# Teensylu2-0_7.net
KiCad netlist of a schematic drawn in EAGLE
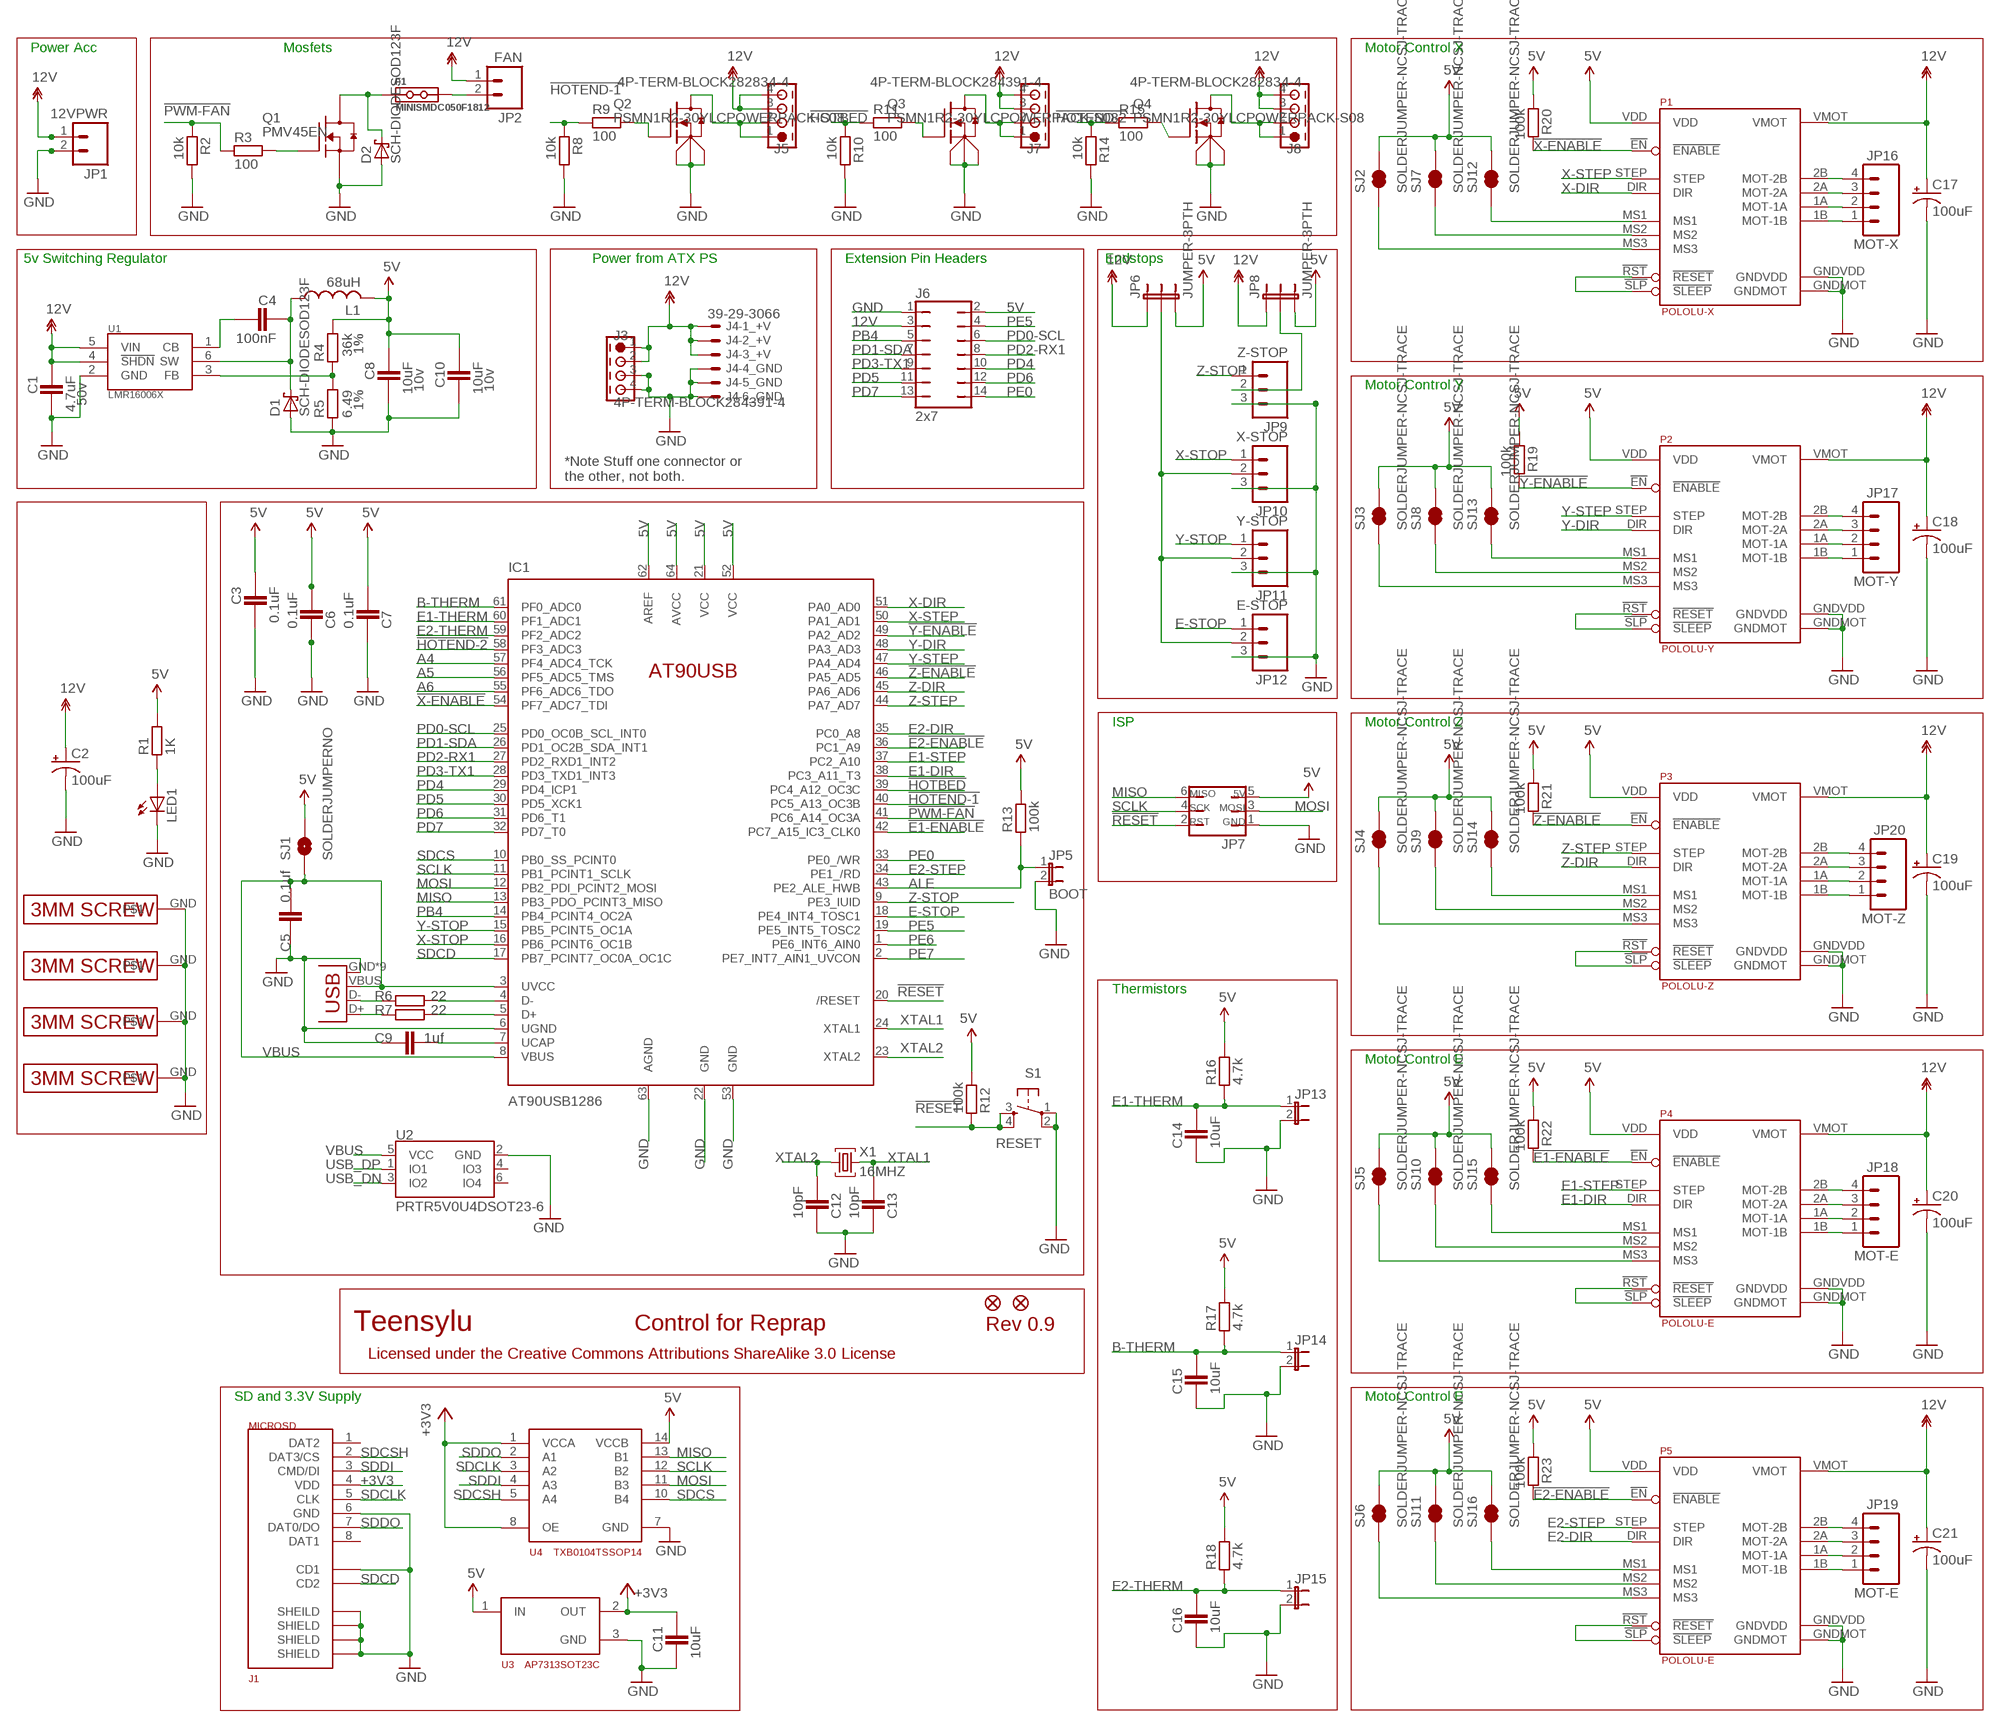
[diagram p0: schematic, sheet 1]

(export (version "E")
  (design (tool "Eeschema 10.0.6"))
  (components
    (comp (ref "C1")
      (value "4.7uF")
      (footprint "eagle-import:CAPC2012X145AN")
      (fields (field (name "VDC") "50v"))
      (libsource (lib "eagle-import") (part "CAPACITOR_0805"))
    )
    (comp (ref "C2")
      (value "100uF")
      (footprint "eagle-import:PANASONIC_D")
      (fields
        (field (name "MANUFACTURER") "Panasonic")
        (field (name "MANUFACTURER_PART_NUMBER") "EEE-FTH101XAP")
        (field (name "TOLERANCE") "20%")
      )
      (libsource (lib "eagle-import") (part "CPOL-USD"))
    )
    (comp (ref "C3")
      (value "0.1uF")
      (footprint "eagle-import:CAPC1608X92N")
      (libsource (lib "eagle-import") (part "CAPACITOR_0603"))
    )
    (comp (ref "C4")
      (value "100nF")
      (footprint "eagle-import:CAPC1608X92N")
      (libsource (lib "eagle-import") (part "CAPACITOR_0603"))
    )
    (comp (ref "C5")
      (value "0.1uf")
      (footprint "eagle-import:CAPC1608X92N")
      (libsource (lib "eagle-import") (part "CAPACITOR_0603"))
    )
    (comp (ref "C6")
      (value "0.1uF")
      (footprint "eagle-import:CAPC1608X92N")
      (libsource (lib "eagle-import") (part "CAPACITOR_0603"))
    )
    (comp (ref "C7")
      (value "0.1uF")
      (footprint "eagle-import:CAPC1608X92N")
      (libsource (lib "eagle-import") (part "CAPACITOR_0603"))
    )
    (comp (ref "C8")
      (value "10uF")
      (footprint "eagle-import:CAPC2012X145AN")
      (fields (field (name "VDC") "10v"))
      (libsource (lib "eagle-import") (part "CAPACITOR_0805"))
    )
    (comp (ref "C9")
      (value "1uf")
      (footprint "eagle-import:CAPC1608X92N")
      (libsource (lib "eagle-import") (part "CAPACITOR_0603"))
    )
    (comp (ref "C10")
      (value "10uF")
      (footprint "eagle-import:CAPC2012X145AN")
      (fields (field (name "VDC") "10v"))
      (libsource (lib "eagle-import") (part "CAPACITOR_0805"))
    )
    (comp (ref "C11")
      (value "10uF")
      (footprint "eagle-import:CAPC1608X92N")
      (libsource (lib "eagle-import") (part "CAPACITOR_0603"))
    )
    (comp (ref "C12")
      (value "10pF")
      (footprint "eagle-import:CAPC1608X92N")
      (libsource (lib "eagle-import") (part "CAPACITOR_0603"))
    )
    (comp (ref "C13")
      (value "10pF")
      (footprint "eagle-import:CAPC1608X92N")
      (libsource (lib "eagle-import") (part "CAPACITOR_0603"))
    )
    (comp (ref "C14")
      (value "10uF")
      (footprint "eagle-import:CAPC1608X92N")
      (libsource (lib "eagle-import") (part "CAPACITOR_0603"))
    )
    (comp (ref "C15")
      (value "10uF")
      (footprint "eagle-import:CAPC1608X92N")
      (libsource (lib "eagle-import") (part "CAPACITOR_0603"))
    )
    (comp (ref "C16")
      (value "10uF")
      (footprint "eagle-import:CAPC1608X92N")
      (libsource (lib "eagle-import") (part "CAPACITOR_0603"))
    )
    (comp (ref "C17")
      (value "100uF")
      (footprint "eagle-import:PANASONIC_D")
      (fields
        (field (name "MANUFACTURER") "Panasonic")
        (field (name "MANUFACTURER_PART_NUMBER") "EEE-FTH101XAP")
        (field (name "TOLERANCE") "20%")
      )
      (libsource (lib "eagle-import") (part "CPOL-USD"))
    )
    (comp (ref "C18")
      (value "100uF")
      (footprint "eagle-import:PANASONIC_D")
      (fields
        (field (name "MANUFACTURER") "Panasonic")
        (field (name "MANUFACTURER_PART_NUMBER") "EEE-FTH101XAP")
        (field (name "TOLERANCE") "20%")
      )
      (libsource (lib "eagle-import") (part "CPOL-USD"))
    )
    (comp (ref "C19")
      (value "100uF")
      (footprint "eagle-import:PANASONIC_D")
      (fields
        (field (name "MANUFACTURER") "Panasonic")
        (field (name "MANUFACTURER_PART_NUMBER") "EEE-FTH101XAP")
        (field (name "TOLERANCE") "20%")
      )
      (libsource (lib "eagle-import") (part "CPOL-USD"))
    )
    (comp (ref "C20")
      (value "100uF")
      (footprint "eagle-import:PANASONIC_D")
      (fields
        (field (name "MANUFACTURER") "Panasonic")
        (field (name "MANUFACTURER_PART_NUMBER") "EEE-FTH101XAP")
        (field (name "TOLERANCE") "20%")
      )
      (libsource (lib "eagle-import") (part "CPOL-USD"))
    )
    (comp (ref "C21")
      (value "100uF")
      (footprint "eagle-import:PANASONIC_D")
      (fields
        (field (name "MANUFACTURER") "Panasonic")
        (field (name "MANUFACTURER_PART_NUMBER") "EEE-FTH101XAP")
        (field (name "TOLERANCE") "20%")
      )
      (libsource (lib "eagle-import") (part "CPOL-USD"))
    )
    (comp (ref "D1")
      (value "SCH-DIODESOD123F")
      (footprint "eagle-import:SOD123F")
      (fields
        (field (name "MANUFACTURER") "NXP Semiconductors")
        (field (name "MANUFACTURER_PART_NUMBER") "PMEG4010CEH,115")
        (field (name "CURRENT") "1A")
        (field (name "MANUFACTURER_1") "NXP Semiconductors")
        (field (name "MANUFACTURER_PART_NUMBER_1") "PMEG4010CEH,115")
        (field (name "REVERSE_VOLTAGE") "40V")
      )
      (libsource (lib "eagle-import") (part "SCH-DIODESOD123F"))
    )
    (comp (ref "D2")
      (value "SCH-DIODESOD123F")
      (footprint "eagle-import:SOD123F")
      (fields
        (field (name "MANUFACTURER") "NXP Semiconductors")
        (field (name "MANUFACTURER_PART_NUMBER") "PMEG4010CEH,115")
        (field (name "CURRENT") "1A")
        (field (name "MANUFACTURER_1") "NXP Semiconductors")
      )
      (libsource (lib "eagle-import") (part "SCH-DIODESOD123F"))
    )
    (comp (ref "F1")
      (value "MINISMDC050F1812")
      (footprint "eagle-import:MINISMDC")
      (fields
        (field (name "MANUFACTURER") "TE Connectivity")
        (field (name "MANUFACTURER_PART_NUMBER") "MINISMDC050F-2")
      )
      (libsource (lib "eagle-import") (part "MINISMDC050F1812"))
    )
    (comp (ref "IC1")
      (value "AT90USB1286")
      (footprint "eagle-import:TQFP64-2")
      (libsource (lib "eagle-import") (part "AT90USB"))
    )
    (comp (ref "J1")
      (value "MICROSD")
      (footprint "eagle-import:AMPHENOL-MICROSD")
      (fields
        (field (name "MANUFACTURER") "Amphenol")
        (field (name "MANUFACTURER_PART_NUMBER") "114-00841-68")
      )
      (libsource (lib "eagle-import") (part "MICROSD"))
    )
    (comp (ref "J2")
      (value "USB-MICRO-PTH")
      (footprint "eagle-import:USB-MICROB-PTH")
      (fields (field (name "MANUFACTURER") "FCI") (field (name "MANUFACTURER_PART_NUMBER") "10118194-0001LF"))
      (libsource (lib "eagle-import") (part "USB-MICRO-PTH"))
    )
    (comp (ref "J3")
      (value "4P-TERM-BLOCK284391-4")
      (footprint "eagle-import:284391-4")
      (fields
        (field (name "MANUFACTURER") "TE Connectivity")
        (field (name "MANUFACTURER_PART_NUMBER") "284391-4")
      )
      (libsource (lib "eagle-import") (part "4P-TERM-BLOCK284391-4"))
    )
    (comp (ref "J4")
      (value "39-29-3066")
      (footprint "eagle-import:39-29-3066")
      (fields (field (name "MANUFACTURER") "Molex") (field (name "MANUFACTURER_PART_NUMBER") "0039293066"))
      (libsource (lib "eagle-import") (part "39-29-3066"))
    )
    (comp (ref "J5")
      (value "4P-TERM-BLOCK282834-4")
      (footprint "eagle-import:282834-4")
      (fields
        (field (name "MANUFACTURER") "TE Connectivity")
        (field (name "MANUFACTURER_PART_NUMBER") "282834-4")
      )
      (libsource (lib "eagle-import") (part "4P-TERM-BLOCK282834-4"))
    )
    (comp (ref "J6")
      (value "2x7")
      (footprint "eagle-import:JP7Q")
      (libsource (lib "eagle-import") (part "JP7Q"))
    )
    (comp (ref "J7")
      (value "4P-TERM-BLOCK284391-4")
      (footprint "eagle-import:284391-4")
      (fields
        (field (name "MANUFACTURER") "TE Connectivity")
        (field (name "MANUFACTURER_PART_NUMBER") "284391-4")
      )
      (libsource (lib "eagle-import") (part "4P-TERM-BLOCK284391-4"))
    )
    (comp (ref "J8")
      (value "4P-TERM-BLOCK282834-4")
      (footprint "eagle-import:282834-4")
      (fields
        (field (name "MANUFACTURER") "TE Connectivity")
        (field (name "MANUFACTURER_PART_NUMBER") "282834-4")
      )
      (libsource (lib "eagle-import") (part "4P-TERM-BLOCK282834-4"))
    )
    (comp (ref "JP1")
      (value "12VPWR")
      (footprint "eagle-import:MOLEX-1X2")
      (libsource (lib "eagle-import") (part "M02POLAR"))
    )
    (comp (ref "JP2")
      (value "FAN")
      (footprint "eagle-import:MOLEX-1X2")
      (libsource (lib "eagle-import") (part "M02POLAR"))
    )
    (comp (ref "JP3")
      (value "FIDUCIAL1X2.5")
      (footprint "eagle-import:FIDUCIAL-1X2.5")
      (libsource (lib "eagle-import") (part "FIDUCIAL1X2.5"))
    )
    (comp (ref "JP4")
      (value "FIDUCIAL1X2.5")
      (footprint "eagle-import:FIDUCIAL-1X2.5")
      (libsource (lib "eagle-import") (part "FIDUCIAL1X2.5"))
    )
    (comp (ref "JP5")
      (value "BOOT")
      (footprint "eagle-import:1X02")
      (libsource (lib "eagle-import") (part "JUMPER-2PTH"))
    )
    (comp (ref "JP6")
      (value "JUMPER-3PTH")
      (footprint "eagle-import:1X03")
      (libsource (lib "eagle-import") (part "JUMPER-3PTH"))
    )
    (comp (ref "JP7")
      (value "PROGHEADER")
      (footprint "eagle-import:ISP")
      (libsource (lib "eagle-import") (part "PROGHEADER"))
    )
    (comp (ref "JP8")
      (value "JUMPER-3PTH")
      (footprint "eagle-import:1X03")
      (libsource (lib "eagle-import") (part "JUMPER-3PTH"))
    )
    (comp (ref "JP9")
      (value "Z-STOP")
      (footprint "eagle-import:MOLEX-1X3")
      (libsource (lib "eagle-import") (part "M03POLAR"))
    )
    (comp (ref "JP10")
      (value "X-STOP")
      (footprint "eagle-import:MOLEX-1X3")
      (libsource (lib "eagle-import") (part "M03POLAR"))
    )
    (comp (ref "JP11")
      (value "Y-STOP")
      (footprint "eagle-import:MOLEX-1X3")
      (libsource (lib "eagle-import") (part "M03POLAR"))
    )
    (comp (ref "JP12")
      (value "E-STOP")
      (footprint "eagle-import:MOLEX-1X3")
      (libsource (lib "eagle-import") (part "M03POLAR"))
    )
    (comp (ref "JP13")
      (value "JUMPER-2PTH")
      (footprint "eagle-import:1X02")
      (libsource (lib "eagle-import") (part "JUMPER-2PTH"))
    )
    (comp (ref "JP14")
      (value "JUMPER-2PTH")
      (footprint "eagle-import:1X02")
      (libsource (lib "eagle-import") (part "JUMPER-2PTH"))
    )
    (comp (ref "JP15")
      (value "JUMPER-2PTH")
      (footprint "eagle-import:1X02")
      (libsource (lib "eagle-import") (part "JUMPER-2PTH"))
    )
    (comp (ref "JP16")
      (value "MOT-X")
      (footprint "eagle-import:MOLEX-1X4")
      (libsource (lib "eagle-import") (part "M04POLAR"))
    )
    (comp (ref "JP17")
      (value "MOT-Y")
      (footprint "eagle-import:MOLEX-1X4")
      (libsource (lib "eagle-import") (part "M04POLAR"))
    )
    (comp (ref "JP18")
      (value "MOT-E")
      (footprint "eagle-import:MOLEX-1X4")
      (libsource (lib "eagle-import") (part "M04POLAR"))
    )
    (comp (ref "JP19")
      (value "MOT-E")
      (footprint "eagle-import:MOLEX-1X4")
      (libsource (lib "eagle-import") (part "M04POLAR"))
    )
    (comp (ref "JP20")
      (value "MOT-Z")
      (footprint "eagle-import:MOLEX-1X4")
      (libsource (lib "eagle-import") (part "M04POLAR"))
    )
    (comp (ref "L1")
      (value "68uH")
      (footprint "eagle-import:SRN6045")
      (fields
        (field (name "MANUFACTURER") "Bourns")
        (field (name "MANUFACTURER_PART_NUMBER") "SRN6045-680M")
        (field (name "MANUFACTURER_1") "Bourns")
        (field (name "MANUFACTURER_PART_NUMBER_1") "SRN6045-680M")
      )
      (libsource (lib "eagle-import") (part "INDUCTORSRN6045"))
    )
    (comp (ref "LED1")
      (value "LEDCHIPLED_0805")
      (footprint "eagle-import:CHIPLED_0805")
      (libsource (lib "eagle-import") (part "LEDCHIPLED_0805"))
    )
    (comp (ref "P1")
      (value "POLOLU-X")
      (footprint "eagle-import:POLOLU-STEPPER-PTH")
      (libsource (lib "eagle-import") (part "POLOLU-ALLEGRO"))
    )
    (comp (ref "P2")
      (value "POLOLU-Y")
      (footprint "eagle-import:POLOLU-STEPPER-PTH")
      (libsource (lib "eagle-import") (part "POLOLU-ALLEGRO"))
    )
    (comp (ref "P3")
      (value "POLOLU-Z")
      (footprint "eagle-import:POLOLU-STEPPER-PTH")
      (libsource (lib "eagle-import") (part "POLOLU-ALLEGRO"))
    )
    (comp (ref "P4")
      (value "POLOLU-E")
      (footprint "eagle-import:POLOLU-STEPPER-PTH")
      (libsource (lib "eagle-import") (part "POLOLU-ALLEGRO"))
    )
    (comp (ref "P5")
      (value "POLOLU-E")
      (footprint "eagle-import:POLOLU-STEPPER-PTH")
      (libsource (lib "eagle-import") (part "POLOLU-ALLEGRO"))
    )
    (comp (ref "Q1")
      (value "PMV45EN")
      (footprint "eagle-import:SOT23C")
      (fields
        (field (name "MANUFACTURER") "International Rectifier")
        (field (name "MANUFACTURER_PART_NUMBER") "IRLML2060TRPBF")
        (field (name "VOLTAGE") "60V")
      )
      (libsource (lib "eagle-import") (part "MOSFET-NCH_SOT-23"))
    )
    (comp (ref "Q2")
      (value "PSMN1R2-30YLCPOWERPACK-S08")
      (footprint "eagle-import:LFPACK-POWERPAK-SO8")
      (fields
        (field (name "MANUFACTURER") "NXP Semiconductors")
        (field (name "MANUFACTURER_PART_NUMBER") "PSMN1R2-30YLC,115")
        (field (name "VOLTAGE") "30V")
      )
      (libsource (lib "eagle-import") (part "PSMN1R2-30YLCPOWERPACK-S08"))
    )
    (comp (ref "Q3")
      (value "PSMN1R2-30YLCPOWERPACK-S08")
      (footprint "eagle-import:LFPACK-POWERPAK-SO8")
      (fields
        (field (name "MANUFACTURER") "NXP Semiconductors")
        (field (name "MANUFACTURER_PART_NUMBER") "PSMN1R2-30YLC,115")
        (field (name "VOLTAGE") "30V")
      )
      (libsource (lib "eagle-import") (part "PSMN1R2-30YLCPOWERPACK-S08"))
    )
    (comp (ref "Q4")
      (value "PSMN1R2-30YLCPOWERPACK-S08")
      (footprint "eagle-import:LFPACK-POWERPAK-SO8")
      (fields
        (field (name "MANUFACTURER") "NXP Semiconductors")
        (field (name "MANUFACTURER_PART_NUMBER") "PSMN1R2-30YLC,115")
        (field (name "VOLTAGE") "30V")
      )
      (libsource (lib "eagle-import") (part "PSMN1R2-30YLCPOWERPACK-S08"))
    )
    (comp (ref "R1")
      (value "1K")
      (footprint "eagle-import:RESC1608X55N")
      (libsource (lib "eagle-import") (part "RESISTOR_0603"))
    )
    (comp (ref "R2")
      (value "10k")
      (footprint "eagle-import:RESC1608X55N")
      (libsource (lib "eagle-import") (part "RESISTOR_0603"))
    )
    (comp (ref "R3")
      (value "100")
      (footprint "eagle-import:RESC1608X55N")
      (libsource (lib "eagle-import") (part "RESISTOR_0603"))
    )
    (comp (ref "R4")
      (value "36k")
      (footprint "eagle-import:RESC1608X55N")
      (fields (field (name "TOLERANCE") "1%"))
      (libsource (lib "eagle-import") (part "RESISTOR_0603"))
    )
    (comp (ref "R5")
      (value "6.49")
      (footprint "eagle-import:RESC1608X55N")
      (fields (field (name "TOLERANCE") "1%"))
      (libsource (lib "eagle-import") (part "RESISTOR_0603"))
    )
    (comp (ref "R6")
      (value "22")
      (footprint "eagle-import:RESC1608X55N")
      (libsource (lib "eagle-import") (part "RESISTOR_0603"))
    )
    (comp (ref "R7")
      (value "22")
      (footprint "eagle-import:RESC1608X55N")
      (libsource (lib "eagle-import") (part "RESISTOR_0603"))
    )
    (comp (ref "R8")
      (value "10k")
      (footprint "eagle-import:RESC1608X55N")
      (libsource (lib "eagle-import") (part "RESISTOR_0603"))
    )
    (comp (ref "R9")
      (value "100")
      (footprint "eagle-import:RESC1608X55N")
      (libsource (lib "eagle-import") (part "RESISTOR_0603"))
    )
    (comp (ref "R10")
      (value "10k")
      (footprint "eagle-import:RESC1608X55N")
      (libsource (lib "eagle-import") (part "RESISTOR_0603"))
    )
    (comp (ref "R11")
      (value "100")
      (footprint "eagle-import:RESC1608X55N")
      (libsource (lib "eagle-import") (part "RESISTOR_0603"))
    )
    (comp (ref "R12")
      (value "100k")
      (footprint "eagle-import:RESC1608X55N")
      (libsource (lib "eagle-import") (part "RESISTOR_0603"))
    )
    (comp (ref "R13")
      (value "100k")
      (footprint "eagle-import:RESC1608X55N")
      (libsource (lib "eagle-import") (part "RESISTOR_0603"))
    )
    (comp (ref "R14")
      (value "10k")
      (footprint "eagle-import:RESC1608X55N")
      (libsource (lib "eagle-import") (part "RESISTOR_0603"))
    )
    (comp (ref "R15")
      (value "100")
      (footprint "eagle-import:RESC1608X55N")
      (libsource (lib "eagle-import") (part "RESISTOR_0603"))
    )
    (comp (ref "R16")
      (value "4.7k")
      (footprint "eagle-import:RESC1608X55N")
      (libsource (lib "eagle-import") (part "RESISTOR_0603"))
    )
    (comp (ref "R17")
      (value "4.7k")
      (footprint "eagle-import:RESC1608X55N")
      (libsource (lib "eagle-import") (part "RESISTOR_0603"))
    )
    (comp (ref "R18")
      (value "4.7k")
      (footprint "eagle-import:RESC1608X55N")
      (libsource (lib "eagle-import") (part "RESISTOR_0603"))
    )
    (comp (ref "R19")
      (value "100k")
      (footprint "eagle-import:RESC1608X55N")
      (libsource (lib "eagle-import") (part "RESISTOR_0603"))
    )
    (comp (ref "R20")
      (value "100k")
      (footprint "eagle-import:RESC1608X55N")
      (libsource (lib "eagle-import") (part "RESISTOR_0603"))
    )
    (comp (ref "R21")
      (value "100k")
      (footprint "eagle-import:RESC1608X55N")
      (libsource (lib "eagle-import") (part "RESISTOR_0603"))
    )
    (comp (ref "R22")
      (value "100k")
      (footprint "eagle-import:RESC1608X55N")
      (libsource (lib "eagle-import") (part "RESISTOR_0603"))
    )
    (comp (ref "R23")
      (value "100k")
      (footprint "eagle-import:RESC1608X55N")
      (libsource (lib "eagle-import") (part "RESISTOR_0603"))
    )
    (comp (ref "S1")
      (value "RESET")
      (footprint "eagle-import:TACTILE-PTH")
      (libsource (lib "eagle-import") (part "TAC_SWITCHPTH"))
    )
    (comp (ref "SCREW1")
      (value "3MM-SCREW")
      (footprint "eagle-import:PLATEDSCREW")
      (libsource (lib "eagle-import") (part "3MM-SCREW"))
    )
    (comp (ref "SCREW2")
      (value "3MM-SCREW")
      (footprint "eagle-import:PLATEDSCREW")
      (libsource (lib "eagle-import") (part "3MM-SCREW"))
    )
    (comp (ref "SCREW3")
      (value "3MM-SCREW")
      (footprint "eagle-import:PLATEDSCREW")
      (libsource (lib "eagle-import") (part "3MM-SCREW"))
    )
    (comp (ref "SCREW4")
      (value "3MM-SCREW")
      (footprint "eagle-import:PLATEDSCREW")
      (libsource (lib "eagle-import") (part "3MM-SCREW"))
    )
    (comp (ref "SJ1")
      (value "SOLDERJUMPERNO")
      (footprint "eagle-import:SJ_2S-NO")
      (libsource (lib "eagle-import") (part "SOLDERJUMPERNO"))
    )
    (comp (ref "SJ2")
      (value "SOLDERJUMPER-NCSJ-TRACE")
      (footprint "eagle-import:SJ_2S-TRACE")
      (libsource (lib "eagle-import") (part "SOLDERJUMPER-NCSJ-TRACE"))
    )
    (comp (ref "SJ3")
      (value "SOLDERJUMPER-NCSJ-TRACE")
      (footprint "eagle-import:SJ_2S-TRACE")
      (libsource (lib "eagle-import") (part "SOLDERJUMPER-NCSJ-TRACE"))
    )
    (comp (ref "SJ4")
      (value "SOLDERJUMPER-NCSJ-TRACE")
      (footprint "eagle-import:SJ_2S-TRACE")
      (libsource (lib "eagle-import") (part "SOLDERJUMPER-NCSJ-TRACE"))
    )
    (comp (ref "SJ5")
      (value "SOLDERJUMPER-NCSJ-TRACE")
      (footprint "eagle-import:SJ_2S-TRACE")
      (libsource (lib "eagle-import") (part "SOLDERJUMPER-NCSJ-TRACE"))
    )
    (comp (ref "SJ6")
      (value "SOLDERJUMPER-NCSJ-TRACE")
      (footprint "eagle-import:SJ_2S-TRACE")
      (libsource (lib "eagle-import") (part "SOLDERJUMPER-NCSJ-TRACE"))
    )
    (comp (ref "SJ7")
      (value "SOLDERJUMPER-NCSJ-TRACE")
      (footprint "eagle-import:SJ_2S-TRACE")
      (libsource (lib "eagle-import") (part "SOLDERJUMPER-NCSJ-TRACE"))
    )
    (comp (ref "SJ8")
      (value "SOLDERJUMPER-NCSJ-TRACE")
      (footprint "eagle-import:SJ_2S-TRACE")
      (libsource (lib "eagle-import") (part "SOLDERJUMPER-NCSJ-TRACE"))
    )
    (comp (ref "SJ9")
      (value "SOLDERJUMPER-NCSJ-TRACE")
      (footprint "eagle-import:SJ_2S-TRACE")
      (libsource (lib "eagle-import") (part "SOLDERJUMPER-NCSJ-TRACE"))
    )
    (comp (ref "SJ10")
      (value "SOLDERJUMPER-NCSJ-TRACE")
      (footprint "eagle-import:SJ_2S-TRACE")
      (libsource (lib "eagle-import") (part "SOLDERJUMPER-NCSJ-TRACE"))
    )
    (comp (ref "SJ11")
      (value "SOLDERJUMPER-NCSJ-TRACE")
      (footprint "eagle-import:SJ_2S-TRACE")
      (libsource (lib "eagle-import") (part "SOLDERJUMPER-NCSJ-TRACE"))
    )
    (comp (ref "SJ12")
      (value "SOLDERJUMPER-NCSJ-TRACE")
      (footprint "eagle-import:SJ_2S-TRACE")
      (libsource (lib "eagle-import") (part "SOLDERJUMPER-NCSJ-TRACE"))
    )
    (comp (ref "SJ13")
      (value "SOLDERJUMPER-NCSJ-TRACE")
      (footprint "eagle-import:SJ_2S-TRACE")
      (libsource (lib "eagle-import") (part "SOLDERJUMPER-NCSJ-TRACE"))
    )
    (comp (ref "SJ14")
      (value "SOLDERJUMPER-NCSJ-TRACE")
      (footprint "eagle-import:SJ_2S-TRACE")
      (libsource (lib "eagle-import") (part "SOLDERJUMPER-NCSJ-TRACE"))
    )
    (comp (ref "SJ15")
      (value "SOLDERJUMPER-NCSJ-TRACE")
      (footprint "eagle-import:SJ_2S-TRACE")
      (libsource (lib "eagle-import") (part "SOLDERJUMPER-NCSJ-TRACE"))
    )
    (comp (ref "SJ16")
      (value "SOLDERJUMPER-NCSJ-TRACE")
      (footprint "eagle-import:SJ_2S-TRACE")
      (libsource (lib "eagle-import") (part "SOLDERJUMPER-NCSJ-TRACE"))
    )
    (comp (ref "U1")
      (value "LMR16006X")
      (footprint "eagle-import:TSOT6")
      (fields
        (field (name "MANUFACTURER") "Texas Instruments")
        (field (name "MANUFACTURER_PART_NUMBER") "LMR16006XDDCT")
      )
      (libsource (lib "eagle-import") (part "LMR16006X"))
    )
    (comp (ref "U2")
      (value "PRTR5V0U4DSOT23-6")
      (footprint "eagle-import:SOT23-6")
      (fields
        (field (name "MANUFACTURER") "NXP Semiconductors")
        (field (name "MANUFACTURER_PART_NUMBER") "PRTR5V0U4D,125")
      )
      (libsource (lib "eagle-import") (part "PRTR5V0U4DSOT23-6"))
    )
    (comp (ref "U3")
      (value "AP7313SOT23C")
      (footprint "eagle-import:SOT23C")
      (fields
        (field (name "MANUFACTURER") "Diodes Incorporated")
        (field (name "MANUFACTURER_PART_NUMBER") "AP7313-33SAG-7")
      )
      (libsource (lib "eagle-import") (part "AP7313SOT23C"))
    )
    (comp (ref "U4")
      (value "TXB0104TSSOP14")
      (footprint "eagle-import:TSSOP14")
      (fields
        (field (name "MANUFACTURER") "Texas Instruments")
        (field (name "MANUFACTURER_PART_NUMBER") "TXB0104PWR")
      )
      (libsource (lib "eagle-import") (part "TXB0104TSSOP14"))
    )
    (comp (ref "X1")
      (value "16MHZ")
      (footprint "eagle-import:NDK-XTAL")
      (libsource (lib "eagle-import") (part "XTAL"))
    )
  )
  (nets
    (net (code "1") (name "+3V3") (class "Default")
      (node (ref "C11") (pin "1") (pinfunction "1_1") (pintype "passive"))
      (node (ref "J1") (pin "4") (pinfunction "VDD_4") (pintype "power_in"))
      (node (ref "U3") (pin "2") (pinfunction "OUT_2") (pintype "power_in"))
      (node (ref "U4") (pin "1") (pinfunction "VCCA_1") (pintype "power_in"))
      (node (ref "U4") (pin "8") (pinfunction "OE_8") (pintype "input"))
    )
    (net (code "2") (name "/A4") (class "Default")
      (node (ref "IC1") (pin "57") (pinfunction "PF4_ADC4_TCK_57") (pintype "bidirectional"))
    )
    (net (code "3") (name "/A5") (class "Default")
      (node (ref "IC1") (pin "56") (pinfunction "PF5_ADC5_TMS_56") (pintype "bidirectional"))
    )
    (net (code "4") (name "/A6") (class "Default")
      (node (ref "IC1") (pin "55") (pinfunction "PF6_ADC6_TDO_55") (pintype "bidirectional"))
    )
    (net (code "5") (name "/ALE") (class "Default")
      (node (ref "IC1") (pin "43") (pinfunction "PE2_ALE_HWB_43") (pintype "bidirectional"))
      (node (ref "JP5") (pin "1") (pinfunction "1_1") (pintype "passive"))
      (node (ref "R13") (pin "1") (pinfunction "1_1") (pintype "passive"))
    )
    (net (code "6") (name "/B-THERM") (class "Default")
      (node (ref "C15") (pin "2") (pinfunction "2_2") (pintype "passive"))
      (node (ref "IC1") (pin "61") (pinfunction "PF0_ADC0_61") (pintype "bidirectional"))
      (node (ref "JP14") (pin "1") (pinfunction "1_1") (pintype "passive"))
      (node (ref "R17") (pin "1") (pinfunction "1_1") (pintype "passive"))
    )
    (net (code "7") (name "/E-STOP") (class "Default")
      (node (ref "IC1") (pin "18") (pinfunction "PE4_INT4_TOSC1_18") (pintype "bidirectional"))
      (node (ref "JP12") (pin "1") (pinfunction "1_1") (pintype "passive"))
    )
    (net (code "8") (name "/E1-DIR") (class "Default")
      (node (ref "IC1") (pin "38") (pinfunction "PC3_A11_T3_38") (pintype "bidirectional"))
      (node (ref "P4") (pin "DIR") (pinfunction "DIR_DIR") (pintype "bidirectional"))
    )
    (net (code "9") (name "/E1-STEP") (class "Default")
      (node (ref "IC1") (pin "37") (pinfunction "PC2_A10_37") (pintype "bidirectional"))
      (node (ref "P4") (pin "STEP") (pinfunction "STEP_STEP") (pintype "bidirectional"))
    )
    (net (code "10") (name "/E1-THERM") (class "Default")
      (node (ref "C14") (pin "2") (pinfunction "2_2") (pintype "passive"))
      (node (ref "IC1") (pin "60") (pinfunction "PF1_ADC1_60") (pintype "bidirectional"))
      (node (ref "JP13") (pin "1") (pinfunction "1_1") (pintype "passive"))
      (node (ref "R16") (pin "1") (pinfunction "1_1") (pintype "passive"))
    )
    (net (code "11") (name "/E2-DIR") (class "Default")
      (node (ref "IC1") (pin "35") (pinfunction "PC0_A8_35") (pintype "bidirectional"))
      (node (ref "P5") (pin "DIR") (pinfunction "DIR_DIR") (pintype "bidirectional"))
    )
    (net (code "12") (name "/E2-STEP") (class "Default")
      (node (ref "IC1") (pin "34") (pinfunction "PE1_/RD_34") (pintype "bidirectional"))
      (node (ref "P5") (pin "STEP") (pinfunction "STEP_STEP") (pintype "bidirectional"))
    )
    (net (code "13") (name "/E2-THERM") (class "Default")
      (node (ref "C16") (pin "2") (pinfunction "2_2") (pintype "passive"))
      (node (ref "IC1") (pin "59") (pinfunction "PF2_ADC2_59") (pintype "bidirectional"))
      (node (ref "JP15") (pin "1") (pinfunction "1_1") (pintype "passive"))
      (node (ref "R18") (pin "1") (pinfunction "1_1") (pintype "passive"))
    )
    (net (code "14") (name "/MISO") (class "Default")
      (node (ref "IC1") (pin "13") (pinfunction "PB3_PDO_PCINT3_MISO_13") (pintype "bidirectional"))
      (node (ref "JP7") (pin "6") (pinfunction "6_6") (pintype "passive"))
      (node (ref "U4") (pin "13") (pinfunction "B1_13") (pintype "bidirectional"))
    )
    (net (code "15") (name "/MOSI") (class "Default")
      (node (ref "IC1") (pin "12") (pinfunction "PB2_PDI_PCINT2_MOSI_12") (pintype "bidirectional"))
      (node (ref "JP7") (pin "3") (pinfunction "3_3") (pintype "passive"))
      (node (ref "U4") (pin "11") (pinfunction "B3_11") (pintype "bidirectional"))
    )
    (net (code "16") (name "/PB4") (class "Default")
      (node (ref "IC1") (pin "14") (pinfunction "PB4_PCINT4_OC2A_14") (pintype "bidirectional"))
      (node (ref "J6") (pin "5") (pinfunction "5_5") (pintype "passive"))
    )
    (net (code "17") (name "/PD0-SCL") (class "Default")
      (node (ref "IC1") (pin "25") (pinfunction "PD0_OC0B_SCL_INT0_25") (pintype "bidirectional"))
      (node (ref "J6") (pin "6") (pinfunction "6_6") (pintype "passive"))
    )
    (net (code "18") (name "/PD1-SDA") (class "Default")
      (node (ref "IC1") (pin "26") (pinfunction "PD1_OC2B_SDA_INT1_26") (pintype "bidirectional"))
      (node (ref "J6") (pin "7") (pinfunction "7_7") (pintype "passive"))
    )
    (net (code "19") (name "/PD2-RX1") (class "Default")
      (node (ref "IC1") (pin "27") (pinfunction "PD2_RXD1_INT2_27") (pintype "bidirectional"))
      (node (ref "J6") (pin "8") (pinfunction "8_8") (pintype "passive"))
    )
    (net (code "20") (name "/PD3-TX1") (class "Default")
      (node (ref "IC1") (pin "28") (pinfunction "PD3_TXD1_INT3_28") (pintype "bidirectional"))
      (node (ref "J6") (pin "9") (pinfunction "9_9") (pintype "passive"))
    )
    (net (code "21") (name "/PD4") (class "Default")
      (node (ref "IC1") (pin "29") (pinfunction "PD4_ICP1_29") (pintype "bidirectional"))
      (node (ref "J6") (pin "10") (pinfunction "10_10") (pintype "passive"))
    )
    (net (code "22") (name "/PD5") (class "Default")
      (node (ref "IC1") (pin "30") (pinfunction "PD5_XCK1_30") (pintype "bidirectional"))
      (node (ref "J6") (pin "11") (pinfunction "11_11") (pintype "passive"))
    )
    (net (code "23") (name "/PD6") (class "Default")
      (node (ref "IC1") (pin "31") (pinfunction "PD6_T1_31") (pintype "bidirectional"))
      (node (ref "J6") (pin "12") (pinfunction "12_12") (pintype "passive"))
    )
    (net (code "24") (name "/PD7") (class "Default")
      (node (ref "IC1") (pin "32") (pinfunction "PD7_T0_32") (pintype "bidirectional"))
      (node (ref "J6") (pin "13") (pinfunction "13_13") (pintype "passive"))
    )
    (net (code "25") (name "/PE0") (class "Default")
      (node (ref "IC1") (pin "33") (pinfunction "PE0_/WR_33") (pintype "bidirectional"))
      (node (ref "J6") (pin "14") (pinfunction "14_14") (pintype "passive"))
    )
    (net (code "26") (name "/PE5") (class "Default")
      (node (ref "IC1") (pin "19") (pinfunction "PE5_INT5_TOSC2_19") (pintype "bidirectional"))
      (node (ref "J6") (pin "4") (pinfunction "4_4") (pintype "passive"))
    )
    (net (code "27") (name "/PE6") (class "Default")
      (node (ref "IC1") (pin "1") (pinfunction "PE6_INT6_AIN0_1") (pintype "bidirectional"))
    )
    (net (code "28") (name "/PE7") (class "Default")
      (node (ref "IC1") (pin "2") (pinfunction "PE7_INT7_AIN1_UVCON_2") (pintype "bidirectional"))
    )
    (net (code "29") (name "/SCLK") (class "Default")
      (node (ref "IC1") (pin "11") (pinfunction "PB1_PCINT1_SCLK_11") (pintype "bidirectional"))
      (node (ref "JP7") (pin "4") (pinfunction "4_4") (pintype "passive"))
      (node (ref "U4") (pin "12") (pinfunction "B2_12") (pintype "bidirectional"))
    )
    (net (code "30") (name "/SDCD") (class "Default")
      (node (ref "IC1") (pin "17") (pinfunction "PB7_PCINT7_OC0A_OC1C_17") (pintype "bidirectional"))
      (node (ref "J1") (pin "CD2") (pinfunction "CD2_CD2") (pintype "bidirectional"))
    )
    (net (code "31") (name "/SDCLK") (class "Default")
      (node (ref "J1") (pin "5") (pinfunction "CLK_5") (pintype "input"))
      (node (ref "U4") (pin "3") (pinfunction "A2_3") (pintype "bidirectional"))
    )
    (net (code "32") (name "/SDCS") (class "Default")
      (node (ref "IC1") (pin "10") (pinfunction "PB0_SS_PCINT0_10") (pintype "bidirectional"))
      (node (ref "U4") (pin "10") (pinfunction "B4_10") (pintype "bidirectional"))
    )
    (net (code "33") (name "/SDCSH") (class "Default")
      (node (ref "J1") (pin "2") (pinfunction "DAT3/CS_2") (pintype "bidirectional"))
      (node (ref "U4") (pin "5") (pinfunction "A4_5") (pintype "bidirectional"))
    )
    (net (code "34") (name "/SDDI") (class "Default")
      (node (ref "J1") (pin "3") (pinfunction "CMD/DI_3") (pintype "input"))
      (node (ref "U4") (pin "4") (pinfunction "A3_4") (pintype "bidirectional"))
    )
    (net (code "35") (name "/SDDO") (class "Default")
      (node (ref "J1") (pin "7") (pinfunction "DAT0/DO_7") (pintype "bidirectional"))
      (node (ref "U4") (pin "2") (pinfunction "A1_2") (pintype "bidirectional"))
    )
    (net (code "36") (name "/USB_DN") (class "Default")
      (node (ref "J2") (pin "D-") (pinfunction "D-_D-") (pintype "bidirectional"))
      (node (ref "R6") (pin "1") (pinfunction "1_1") (pintype "passive"))
      (node (ref "U2") (pin "3") (pinfunction "IO2_3") (pintype "bidirectional"))
    )
    (net (code "37") (name "/USB_DP") (class "Default")
      (node (ref "J2") (pin "D+") (pinfunction "D+_D+") (pintype "bidirectional"))
      (node (ref "R7") (pin "1") (pinfunction "1_1") (pintype "passive"))
      (node (ref "U2") (pin "1") (pinfunction "IO1_1") (pintype "bidirectional"))
    )
    (net (code "38") (name "/VBUS") (class "Default")
      (node (ref "C5") (pin "2") (pinfunction "2_2") (pintype "passive"))
      (node (ref "IC1") (pin "3") (pinfunction "UVCC_3") (pintype "power_in"))
      (node (ref "IC1") (pin "8") (pinfunction "VBUS_8") (pintype "bidirectional"))
      (node (ref "J2") (pin "VBUS") (pinfunction "VBUS_VBUS") (pintype "bidirectional"))
      (node (ref "SJ1") (pin "1") (pinfunction "1_1") (pintype "passive"))
      (node (ref "U2") (pin "5") (pinfunction "VCC_5") (pintype "power_in"))
    )
    (net (code "39") (name "/X-DIR") (class "Default")
      (node (ref "IC1") (pin "51") (pinfunction "PA0_AD0_51") (pintype "bidirectional"))
      (node (ref "P1") (pin "DIR") (pinfunction "DIR_DIR") (pintype "bidirectional"))
    )
    (net (code "40") (name "/X-STEP") (class "Default")
      (node (ref "IC1") (pin "50") (pinfunction "PA1_AD1_50") (pintype "bidirectional"))
      (node (ref "P1") (pin "STEP") (pinfunction "STEP_STEP") (pintype "bidirectional"))
    )
    (net (code "41") (name "/X-STOP") (class "Default")
      (node (ref "IC1") (pin "16") (pinfunction "PB6_PCINT6_OC1B_16") (pintype "bidirectional"))
      (node (ref "JP10") (pin "1") (pinfunction "1_1") (pintype "passive"))
    )
    (net (code "42") (name "/XTAL1") (class "Default")
      (node (ref "C13") (pin "2") (pinfunction "2_2") (pintype "passive"))
      (node (ref "IC1") (pin "24") (pinfunction "XTAL1_24") (pintype "passive"))
      (node (ref "X1") (pin "P$2") (pinfunction "2_P$2") (pintype "passive"))
    )
    (net (code "43") (name "/XTAL2") (class "Default")
      (node (ref "C12") (pin "2") (pinfunction "2_2") (pintype "passive"))
      (node (ref "IC1") (pin "23") (pinfunction "XTAL2_23") (pintype "passive"))
      (node (ref "X1") (pin "P$1") (pinfunction "1_P$1") (pintype "passive"))
    )
    (net (code "44") (name "/Y-DIR") (class "Default")
      (node (ref "IC1") (pin "48") (pinfunction "PA3_AD3_48") (pintype "bidirectional"))
      (node (ref "P2") (pin "DIR") (pinfunction "DIR_DIR") (pintype "bidirectional"))
    )
    (net (code "45") (name "/Y-STEP") (class "Default")
      (node (ref "IC1") (pin "47") (pinfunction "PA4_AD4_47") (pintype "bidirectional"))
      (node (ref "P2") (pin "STEP") (pinfunction "STEP_STEP") (pintype "bidirectional"))
    )
    (net (code "46") (name "/Y-STOP") (class "Default")
      (node (ref "IC1") (pin "15") (pinfunction "PB5_PCINT5_OC1A_15") (pintype "bidirectional"))
      (node (ref "JP11") (pin "1") (pinfunction "1_1") (pintype "passive"))
    )
    (net (code "47") (name "/Z-DIR") (class "Default")
      (node (ref "IC1") (pin "45") (pinfunction "PA6_AD6_45") (pintype "bidirectional"))
      (node (ref "P3") (pin "DIR") (pinfunction "DIR_DIR") (pintype "bidirectional"))
    )
    (net (code "48") (name "/Z-STEP") (class "Default")
      (node (ref "IC1") (pin "44") (pinfunction "PA7_AD7_44") (pintype "bidirectional"))
      (node (ref "P3") (pin "STEP") (pinfunction "STEP_STEP") (pintype "bidirectional"))
    )
    (net (code "49") (name "/Z-STOP") (class "Default")
      (node (ref "IC1") (pin "9") (pinfunction "PE3_IUID_9") (pintype "bidirectional"))
      (node (ref "JP9") (pin "1") (pinfunction "1_1") (pintype "passive"))
    )
    (net (code "50") (name "/~{E1-ENABLE}") (class "Default")
      (node (ref "IC1") (pin "42") (pinfunction "PC7_A15_IC3_CLK0_42") (pintype "bidirectional"))
      (node (ref "P4") (pin "!EN") (pinfunction "~{ENABLE}_!EN") (pintype "input"))
      (node (ref "R22") (pin "2") (pinfunction "2_2") (pintype "passive"))
    )
    (net (code "51") (name "/~{E2-ENABLE}") (class "Default")
      (node (ref "IC1") (pin "36") (pinfunction "PC1_A9_36") (pintype "bidirectional"))
      (node (ref "P5") (pin "!EN") (pinfunction "~{ENABLE}_!EN") (pintype "input"))
      (node (ref "R23") (pin "2") (pinfunction "2_2") (pintype "passive"))
    )
    (net (code "52") (name "/~{HOTBED}") (class "Default")
      (node (ref "IC1") (pin "39") (pinfunction "PC4_A12_OC3C_39") (pintype "bidirectional"))
      (node (ref "R10") (pin "1") (pinfunction "1_1") (pintype "passive"))
      (node (ref "R11") (pin "1") (pinfunction "1_1") (pintype "passive"))
    )
    (net (code "53") (name "/~{HOTEND-1}") (class "Default")
      (node (ref "IC1") (pin "40") (pinfunction "PC5_A13_OC3B_40") (pintype "bidirectional"))
      (node (ref "R8") (pin "1") (pinfunction "1_1") (pintype "passive"))
      (node (ref "R9") (pin "1") (pinfunction "1_1") (pintype "passive"))
    )
    (net (code "54") (name "/~{HOTEND-2}") (class "Default")
      (node (ref "IC1") (pin "58") (pinfunction "PF3_ADC3_58") (pintype "bidirectional"))
      (node (ref "R14") (pin "1") (pinfunction "1_1") (pintype "passive"))
      (node (ref "R15") (pin "1") (pinfunction "1_1") (pintype "passive"))
    )
    (net (code "55") (name "/~{PWM-FAN}") (class "Default")
      (node (ref "IC1") (pin "41") (pinfunction "PC6_A14_OC3A_41") (pintype "bidirectional"))
      (node (ref "R2") (pin "1") (pinfunction "1_1") (pintype "passive"))
      (node (ref "R3") (pin "1") (pinfunction "1_1") (pintype "passive"))
    )
    (net (code "56") (name "/~{RESET}") (class "Default")
      (node (ref "IC1") (pin "20") (pinfunction "/RESET_20") (pintype "bidirectional"))
      (node (ref "JP7") (pin "2") (pinfunction "2_2") (pintype "passive"))
      (node (ref "R12") (pin "1") (pinfunction "1_1") (pintype "passive"))
      (node (ref "S1") (pin "3") (pinfunction "3_3") (pintype "passive"))
      (node (ref "S1") (pin "4") (pinfunction "4_4") (pintype "passive"))
    )
    (net (code "57") (name "/~{X-ENABLE}") (class "Default")
      (node (ref "IC1") (pin "54") (pinfunction "PF7_ADC7_TDI_54") (pintype "bidirectional"))
      (node (ref "P1") (pin "!EN") (pinfunction "~{ENABLE}_!EN") (pintype "input"))
      (node (ref "R20") (pin "2") (pinfunction "2_2") (pintype "passive"))
    )
    (net (code "58") (name "/~{Y-ENABLE}") (class "Default")
      (node (ref "IC1") (pin "49") (pinfunction "PA2_AD2_49") (pintype "bidirectional"))
      (node (ref "P2") (pin "!EN") (pinfunction "~{ENABLE}_!EN") (pintype "input"))
      (node (ref "R19") (pin "2") (pinfunction "2_2") (pintype "passive"))
    )
    (net (code "59") (name "/~{Z-ENABLE}") (class "Default")
      (node (ref "IC1") (pin "46") (pinfunction "PA5_AD5_46") (pintype "bidirectional"))
      (node (ref "P3") (pin "!EN") (pinfunction "~{ENABLE}_!EN") (pintype "input"))
      (node (ref "R21") (pin "2") (pinfunction "2_2") (pintype "passive"))
    )
    (net (code "60") (name "5V") (class "Default")
      (node (ref "C10") (pin "1") (pinfunction "1_1") (pintype "passive"))
      (node (ref "C3") (pin "1") (pinfunction "1_1") (pintype "passive"))
      (node (ref "C6") (pin "2") (pinfunction "2_2") (pintype "passive"))
      (node (ref "C7") (pin "2") (pinfunction "2_2") (pintype "passive"))
      (node (ref "C8") (pin "1") (pinfunction "1_1") (pintype "passive"))
      (node (ref "IC1") (pin "21") (pinfunction "VCC_21") (pintype "power_in"))
      (node (ref "IC1") (pin "52") (pinfunction "VCC_52") (pintype "power_in"))
      (node (ref "IC1") (pin "62") (pinfunction "AREF_62") (pintype "power_in"))
      (node (ref "IC1") (pin "64") (pinfunction "AVCC_64") (pintype "power_in"))
      (node (ref "J6") (pin "2") (pinfunction "2_2") (pintype "passive"))
      (node (ref "JP6") (pin "3") (pinfunction "3_3") (pintype "passive"))
      (node (ref "JP7") (pin "5") (pinfunction "5_5") (pintype "passive"))
      (node (ref "JP8") (pin "3") (pinfunction "3_3") (pintype "passive"))
      (node (ref "L1") (pin "2") (pinfunction "2_2") (pintype "passive"))
      (node (ref "P1") (pin "VDD") (pinfunction "VDD_VDD") (pintype "power_in"))
      (node (ref "P2") (pin "VDD") (pinfunction "VDD_VDD") (pintype "power_in"))
      (node (ref "P3") (pin "VDD") (pinfunction "VDD_VDD") (pintype "power_in"))
      (node (ref "P4") (pin "VDD") (pinfunction "VDD_VDD") (pintype "power_in"))
      (node (ref "P5") (pin "VDD") (pinfunction "VDD_VDD") (pintype "power_in"))
      (node (ref "R1") (pin "2") (pinfunction "2_2") (pintype "passive"))
      (node (ref "R12") (pin "2") (pinfunction "2_2") (pintype "passive"))
      (node (ref "R13") (pin "2") (pinfunction "2_2") (pintype "passive"))
      (node (ref "R16") (pin "2") (pinfunction "2_2") (pintype "passive"))
      (node (ref "R17") (pin "2") (pinfunction "2_2") (pintype "passive"))
      (node (ref "R18") (pin "2") (pinfunction "2_2") (pintype "passive"))
      (node (ref "R19") (pin "1") (pinfunction "1_1") (pintype "passive"))
      (node (ref "R20") (pin "1") (pinfunction "1_1") (pintype "passive"))
      (node (ref "R21") (pin "1") (pinfunction "1_1") (pintype "passive"))
      (node (ref "R22") (pin "1") (pinfunction "1_1") (pintype "passive"))
      (node (ref "R23") (pin "1") (pinfunction "1_1") (pintype "passive"))
      (node (ref "R4") (pin "1") (pinfunction "1_1") (pintype "passive"))
      (node (ref "SJ1") (pin "2") (pinfunction "2_2") (pintype "passive"))
      (node (ref "SJ10") (pin "2") (pinfunction "2_2") (pintype "passive"))
      (node (ref "SJ11") (pin "2") (pinfunction "2_2") (pintype "passive"))
      (node (ref "SJ12") (pin "2") (pinfunction "2_2") (pintype "passive"))
      (node (ref "SJ13") (pin "2") (pinfunction "2_2") (pintype "passive"))
      (node (ref "SJ14") (pin "2") (pinfunction "2_2") (pintype "passive"))
      (node (ref "SJ15") (pin "2") (pinfunction "2_2") (pintype "passive"))
      (node (ref "SJ16") (pin "2") (pinfunction "2_2") (pintype "passive"))
      (node (ref "SJ2") (pin "2") (pinfunction "2_2") (pintype "passive"))
      (node (ref "SJ3") (pin "2") (pinfunction "2_2") (pintype "passive"))
      (node (ref "SJ4") (pin "2") (pinfunction "2_2") (pintype "passive"))
      (node (ref "SJ5") (pin "2") (pinfunction "2_2") (pintype "passive"))
      (node (ref "SJ6") (pin "2") (pinfunction "2_2") (pintype "passive"))
      (node (ref "SJ7") (pin "2") (pinfunction "2_2") (pintype "passive"))
      (node (ref "SJ8") (pin "2") (pinfunction "2_2") (pintype "passive"))
      (node (ref "SJ9") (pin "2") (pinfunction "2_2") (pintype "passive"))
      (node (ref "U3") (pin "1") (pinfunction "IN_1") (pintype "power_in"))
      (node (ref "U4") (pin "14") (pinfunction "VCCB_14") (pintype "power_in"))
    )
    (net (code "61") (name "12V") (class "Default")
      (node (ref "C1") (pin "1") (pinfunction "1_1") (pintype "passive"))
      (node (ref "C17") (pin "+") (pinfunction "+_+") (pintype "passive"))
      (node (ref "C18") (pin "+") (pinfunction "+_+") (pintype "passive"))
      (node (ref "C19") (pin "+") (pinfunction "+_+") (pintype "passive"))
      (node (ref "C2") (pin "+") (pinfunction "+_+") (pintype "passive"))
      (node (ref "C20") (pin "+") (pinfunction "+_+") (pintype "passive"))
      (node (ref "C21") (pin "+") (pinfunction "+_+") (pintype "passive"))
      (node (ref "J3") (pin "1") (pinfunction "1_1") (pintype "power_in"))
      (node (ref "J3") (pin "2") (pinfunction "2_2") (pintype "power_in"))
      (node (ref "J4") (pin "1") (pinfunction "S_1") (pintype "passive"))
      (node (ref "J4") (pin "2") (pinfunction "S_2") (pintype "passive"))
      (node (ref "J4") (pin "3") (pinfunction "S_3") (pintype "passive"))
      (node (ref "J5") (pin "3") (pinfunction "3_3") (pintype "power_in"))
      (node (ref "J5") (pin "4") (pinfunction "4_4") (pintype "power_in"))
      (node (ref "J6") (pin "3") (pinfunction "3_3") (pintype "passive"))
      (node (ref "J7") (pin "3") (pinfunction "3_3") (pintype "power_in"))
      (node (ref "J7") (pin "4") (pinfunction "4_4") (pintype "power_in"))
      (node (ref "J8") (pin "3") (pinfunction "3_3") (pintype "power_in"))
      (node (ref "J8") (pin "4") (pinfunction "4_4") (pintype "power_in"))
      (node (ref "JP1") (pin "1") (pinfunction "1_1") (pintype "passive"))
      (node (ref "JP2") (pin "1") (pinfunction "1_1") (pintype "passive"))
      (node (ref "JP6") (pin "1") (pinfunction "1_1") (pintype "passive"))
      (node (ref "JP8") (pin "1") (pinfunction "1_1") (pintype "passive"))
      (node (ref "P1") (pin "VMOT") (pinfunction "VMOT_VMOT") (pintype "power_in"))
      (node (ref "P2") (pin "VMOT") (pinfunction "VMOT_VMOT") (pintype "power_in"))
      (node (ref "P3") (pin "VMOT") (pinfunction "VMOT_VMOT") (pintype "power_in"))
      (node (ref "P4") (pin "VMOT") (pinfunction "VMOT_VMOT") (pintype "power_in"))
      (node (ref "P5") (pin "VMOT") (pinfunction "VMOT_VMOT") (pintype "power_in"))
      (node (ref "U1") (pin "4") (pinfunction "~{SHDN}_4") (pintype "input"))
      (node (ref "U1") (pin "5") (pinfunction "VIN_5") (pintype "power_in"))
    )
    (net (code "62") (name "GND") (class "Default")
      (node (ref "C1") (pin "2") (pinfunction "2_2") (pintype "passive"))
      (node (ref "C10") (pin "2") (pinfunction "2_2") (pintype "passive"))
      (node (ref "C11") (pin "2") (pinfunction "2_2") (pintype "passive"))
      (node (ref "C12") (pin "1") (pinfunction "1_1") (pintype "passive"))
      (node (ref "C13") (pin "1") (pinfunction "1_1") (pintype "passive"))
      (node (ref "C14") (pin "1") (pinfunction "1_1") (pintype "passive"))
      (node (ref "C15") (pin "1") (pinfunction "1_1") (pintype "passive"))
      (node (ref "C16") (pin "1") (pinfunction "1_1") (pintype "passive"))
      (node (ref "C17") (pin "-") (pinfunction "-_-") (pintype "passive"))
      (node (ref "C18") (pin "-") (pinfunction "-_-") (pintype "passive"))
      (node (ref "C19") (pin "-") (pinfunction "-_-") (pintype "passive"))
      (node (ref "C2") (pin "-") (pinfunction "-_-") (pintype "passive"))
      (node (ref "C20") (pin "-") (pinfunction "-_-") (pintype "passive"))
      (node (ref "C21") (pin "-") (pinfunction "-_-") (pintype "passive"))
      (node (ref "C3") (pin "2") (pinfunction "2_2") (pintype "passive"))
      (node (ref "C5") (pin "1") (pinfunction "1_1") (pintype "passive"))
      (node (ref "C6") (pin "1") (pinfunction "1_1") (pintype "passive"))
      (node (ref "C7") (pin "1") (pinfunction "1_1") (pintype "passive"))
      (node (ref "C8") (pin "2") (pinfunction "2_2") (pintype "passive"))
      (node (ref "C9") (pin "1") (pinfunction "1_1") (pintype "passive"))
      (node (ref "D1") (pin "A") (pinfunction "A_A") (pintype "passive"))
      (node (ref "D2") (pin "A") (pinfunction "A_A") (pintype "passive"))
      (node (ref "IC1") (pin "22") (pinfunction "GND_22") (pintype "power_in"))
      (node (ref "IC1") (pin "53") (pinfunction "GND_53") (pintype "power_in"))
      (node (ref "IC1") (pin "6") (pinfunction "UGND_6") (pintype "power_in"))
      (node (ref "IC1") (pin "63") (pinfunction "AGND_63") (pintype "power_in"))
      (node (ref "J1") (pin "6") (pinfunction "GND_6") (pintype "power_in"))
      (node (ref "J1") (pin "C1") (pinfunction "SHEILD_C1") (pintype "bidirectional"))
      (node (ref "J1") (pin "C2") (pinfunction "SHIELD_C2") (pintype "bidirectional"))
      (node (ref "J1") (pin "C3") (pinfunction "SHIELD_C3") (pintype "bidirectional"))
      (node (ref "J1") (pin "C4") (pinfunction "SHIELD_C4") (pintype "bidirectional"))
      (node (ref "J1") (pin "CD1") (pinfunction "CD1_CD1") (pintype "bidirectional"))
      (node (ref "J2") (pin "GND") (pinfunction "GND_GND") (pintype "bidirectional"))
      (node (ref "J2") (pin "GND1") (pinfunction "GND_GND1") (pintype "bidirectional"))
      (node (ref "J2") (pin "GND2") (pinfunction "GND_GND2") (pintype "bidirectional"))
      (node (ref "J2") (pin "GND3") (pinfunction "GND_GND3") (pintype "bidirectional"))
      (node (ref "J2") (pin "GND4") (pinfunction "GND_GND4") (pintype "bidirectional"))
      (node (ref "J2") (pin "GND5") (pinfunction "GND_GND5") (pintype "bidirectional"))
      (node (ref "J2") (pin "GND6") (pinfunction "GND_GND6") (pintype "bidirectional"))
      (node (ref "J2") (pin "GND7") (pinfunction "GND_GND7") (pintype "bidirectional"))
      (node (ref "J2") (pin "GND8") (pinfunction "GND_GND8") (pintype "bidirectional"))
      (node (ref "J3") (pin "3") (pinfunction "3_3") (pintype "power_in"))
      (node (ref "J3") (pin "4") (pinfunction "4_4") (pintype "power_in"))
      (node (ref "J4") (pin "4") (pinfunction "S_4") (pintype "passive"))
      (node (ref "J4") (pin "5") (pinfunction "S_5") (pintype "passive"))
      (node (ref "J4") (pin "6") (pinfunction "S_6") (pintype "passive"))
      (node (ref "J6") (pin "1") (pinfunction "1_1") (pintype "passive"))
      (node (ref "JP1") (pin "2") (pinfunction "2_2") (pintype "passive"))
      (node (ref "JP10") (pin "3") (pinfunction "3_3") (pintype "passive"))
      (node (ref "JP11") (pin "3") (pinfunction "3_3") (pintype "passive"))
      (node (ref "JP12") (pin "3") (pinfunction "3_3") (pintype "passive"))
      (node (ref "JP13") (pin "2") (pinfunction "2_2") (pintype "passive"))
      (node (ref "JP14") (pin "2") (pinfunction "2_2") (pintype "passive"))
      (node (ref "JP15") (pin "2") (pinfunction "2_2") (pintype "passive"))
      (node (ref "JP5") (pin "2") (pinfunction "2_2") (pintype "passive"))
      (node (ref "JP7") (pin "1") (pinfunction "1_1") (pintype "passive"))
      (node (ref "JP9") (pin "3") (pinfunction "3_3") (pintype "passive"))
      (node (ref "LED1") (pin "C") (pinfunction "C_C") (pintype "passive"))
      (node (ref "P1") (pin "GNDMOT") (pinfunction "GNDMOT_GNDMOT") (pintype "power_in"))
      (node (ref "P1") (pin "GNDVDD") (pinfunction "GNDVDD_GNDVDD") (pintype "power_in"))
      (node (ref "P2") (pin "GNDMOT") (pinfunction "GNDMOT_GNDMOT") (pintype "power_in"))
      (node (ref "P2") (pin "GNDVDD") (pinfunction "GNDVDD_GNDVDD") (pintype "power_in"))
      (node (ref "P3") (pin "GNDMOT") (pinfunction "GNDMOT_GNDMOT") (pintype "power_in"))
      (node (ref "P3") (pin "GNDVDD") (pinfunction "GNDVDD_GNDVDD") (pintype "power_in"))
      (node (ref "P4") (pin "GNDMOT") (pinfunction "GNDMOT_GNDMOT") (pintype "power_in"))
      (node (ref "P4") (pin "GNDVDD") (pinfunction "GNDVDD_GNDVDD") (pintype "power_in"))
      (node (ref "P5") (pin "GNDMOT") (pinfunction "GNDMOT_GNDMOT") (pintype "power_in"))
      (node (ref "P5") (pin "GNDVDD") (pinfunction "GNDVDD_GNDVDD") (pintype "power_in"))
      (node (ref "Q1") (pin "2") (pinfunction "S_2") (pintype "passive"))
      (node (ref "Q2") (pin "1") (pinfunction "S1_1") (pintype "passive"))
      (node (ref "Q2") (pin "2") (pinfunction "S2_2") (pintype "passive"))
      (node (ref "Q2") (pin "3") (pinfunction "S3_3") (pintype "passive"))
      (node (ref "Q3") (pin "1") (pinfunction "S1_1") (pintype "passive"))
      (node (ref "Q3") (pin "2") (pinfunction "S2_2") (pintype "passive"))
      (node (ref "Q3") (pin "3") (pinfunction "S3_3") (pintype "passive"))
      (node (ref "Q4") (pin "1") (pinfunction "S1_1") (pintype "passive"))
      (node (ref "Q4") (pin "2") (pinfunction "S2_2") (pintype "passive"))
      (node (ref "Q4") (pin "3") (pinfunction "S3_3") (pintype "passive"))
      (node (ref "R10") (pin "2") (pinfunction "2_2") (pintype "passive"))
      (node (ref "R14") (pin "2") (pinfunction "2_2") (pintype "passive"))
      (node (ref "R2") (pin "2") (pinfunction "2_2") (pintype "passive"))
      (node (ref "R5") (pin "2") (pinfunction "2_2") (pintype "passive"))
      (node (ref "R8") (pin "2") (pinfunction "2_2") (pintype "passive"))
      (node (ref "S1") (pin "1") (pinfunction "1_1") (pintype "passive"))
      (node (ref "S1") (pin "2") (pinfunction "2_2") (pintype "passive"))
      (node (ref "SCREW1") (pin "GND") (pinfunction "P$1_GND") (pintype "bidirectional"))
      (node (ref "SCREW2") (pin "GND") (pinfunction "P$1_GND") (pintype "bidirectional"))
      (node (ref "SCREW3") (pin "GND") (pinfunction "P$1_GND") (pintype "bidirectional"))
      (node (ref "SCREW4") (pin "GND") (pinfunction "P$1_GND") (pintype "bidirectional"))
      (node (ref "U1") (pin "2") (pinfunction "GND_2") (pintype "power_in"))
      (node (ref "U2") (pin "2") (pinfunction "GND_2") (pintype "power_in"))
      (node (ref "U3") (pin "3") (pinfunction "GND_3") (pintype "power_in"))
      (node (ref "U4") (pin "7") (pinfunction "GND_7") (pintype "power_in"))
    )
    (net (code "63") (name "Net-(F1-PadP$2)") (class "Default")
      (node (ref "F1") (pin "P$2") (pinfunction "P$2_P$2") (pintype "passive"))
      (node (ref "JP2") (pin "2") (pinfunction "2_2") (pintype "passive"))
    )
    (net (code "64") (name "Net-(IC1-D+)") (class "Default")
      (node (ref "IC1") (pin "5") (pinfunction "D+_5") (pintype "bidirectional"))
      (node (ref "R7") (pin "2") (pinfunction "2_2") (pintype "passive"))
    )
    (net (code "65") (name "Net-(IC1-D-)") (class "Default")
      (node (ref "IC1") (pin "4") (pinfunction "D-_4") (pintype "bidirectional"))
      (node (ref "R6") (pin "2") (pinfunction "2_2") (pintype "passive"))
    )
    (net (code "66") (name "Net-(IC1-UCAP)") (class "Default")
      (node (ref "C9") (pin "2") (pinfunction "2_2") (pintype "passive"))
      (node (ref "IC1") (pin "7") (pinfunction "UCAP_7") (pintype "power_in"))
    )
    (net (code "67") (name "Net-(JP8-Pad2)") (class "Default")
      (node (ref "JP8") (pin "2") (pinfunction "2_2") (pintype "passive"))
      (node (ref "JP9") (pin "2") (pinfunction "2_2") (pintype "passive"))
    )
    (net (code "68") (name "Net-(JP10-Pad2)") (class "Default")
      (node (ref "JP10") (pin "2") (pinfunction "2_2") (pintype "passive"))
      (node (ref "JP11") (pin "2") (pinfunction "2_2") (pintype "passive"))
      (node (ref "JP12") (pin "2") (pinfunction "2_2") (pintype "passive"))
      (node (ref "JP6") (pin "2") (pinfunction "2_2") (pintype "passive"))
    )
    (net (code "69") (name "Net-(LED1-PadA)") (class "Default")
      (node (ref "LED1") (pin "A") (pinfunction "A_A") (pintype "passive"))
      (node (ref "R1") (pin "1") (pinfunction "1_1") (pintype "passive"))
    )
    (net (code "70") (name "Net-(P1-MOT-1A)") (class "Default")
      (node (ref "JP16") (pin "2") (pinfunction "2_2") (pintype "passive"))
      (node (ref "P1") (pin "1A") (pinfunction "MOT-1A_1A") (pintype "power_in"))
    )
    (net (code "71") (name "Net-(P1-MOT-1B)") (class "Default")
      (node (ref "JP16") (pin "1") (pinfunction "1_1") (pintype "passive"))
      (node (ref "P1") (pin "1B") (pinfunction "MOT-1B_1B") (pintype "power_in"))
    )
    (net (code "72") (name "Net-(P1-MOT-2A)") (class "Default")
      (node (ref "JP16") (pin "3") (pinfunction "3_3") (pintype "passive"))
      (node (ref "P1") (pin "2A") (pinfunction "MOT-2A_2A") (pintype "power_in"))
    )
    (net (code "73") (name "Net-(P1-MOT-2B)") (class "Default")
      (node (ref "JP16") (pin "4") (pinfunction "4_4") (pintype "passive"))
      (node (ref "P1") (pin "2B") (pinfunction "MOT-2B_2B") (pintype "power_in"))
    )
    (net (code "74") (name "Net-(P1-PadMS1)") (class "Default")
      (node (ref "P1") (pin "MS1") (pinfunction "MS1_MS1") (pintype "input"))
      (node (ref "SJ12") (pin "1") (pinfunction "1_1") (pintype "passive"))
    )
    (net (code "75") (name "Net-(P1-PadMS2)") (class "Default")
      (node (ref "P1") (pin "MS2") (pinfunction "MS2_MS2") (pintype "input"))
      (node (ref "SJ7") (pin "1") (pinfunction "1_1") (pintype "passive"))
    )
    (net (code "76") (name "Net-(P1-PadMS3)") (class "Default")
      (node (ref "P1") (pin "MS3") (pinfunction "MS3_MS3") (pintype "input"))
      (node (ref "SJ2") (pin "1") (pinfunction "1_1") (pintype "passive"))
    )
    (net (code "77") (name "Net-(P1-~{RESET})") (class "Default")
      (node (ref "P1") (pin "!RST") (pinfunction "~{RESET}_!RST") (pintype "input"))
      (node (ref "P1") (pin "!SLP") (pinfunction "~{SLEEP}_!SLP") (pintype "input"))
    )
    (net (code "78") (name "Net-(P2-MOT-1A)") (class "Default")
      (node (ref "JP17") (pin "2") (pinfunction "2_2") (pintype "passive"))
      (node (ref "P2") (pin "1A") (pinfunction "MOT-1A_1A") (pintype "power_in"))
    )
    (net (code "79") (name "Net-(P2-MOT-1B)") (class "Default")
      (node (ref "JP17") (pin "1") (pinfunction "1_1") (pintype "passive"))
      (node (ref "P2") (pin "1B") (pinfunction "MOT-1B_1B") (pintype "power_in"))
    )
    (net (code "80") (name "Net-(P2-MOT-2A)") (class "Default")
      (node (ref "JP17") (pin "3") (pinfunction "3_3") (pintype "passive"))
      (node (ref "P2") (pin "2A") (pinfunction "MOT-2A_2A") (pintype "power_in"))
    )
    (net (code "81") (name "Net-(P2-MOT-2B)") (class "Default")
      (node (ref "JP17") (pin "4") (pinfunction "4_4") (pintype "passive"))
      (node (ref "P2") (pin "2B") (pinfunction "MOT-2B_2B") (pintype "power_in"))
    )
    (net (code "82") (name "Net-(P2-PadMS1)") (class "Default")
      (node (ref "P2") (pin "MS1") (pinfunction "MS1_MS1") (pintype "input"))
      (node (ref "SJ13") (pin "1") (pinfunction "1_1") (pintype "passive"))
    )
    (net (code "83") (name "Net-(P2-PadMS2)") (class "Default")
      (node (ref "P2") (pin "MS2") (pinfunction "MS2_MS2") (pintype "input"))
      (node (ref "SJ8") (pin "1") (pinfunction "1_1") (pintype "passive"))
    )
    (net (code "84") (name "Net-(P2-PadMS3)") (class "Default")
      (node (ref "P2") (pin "MS3") (pinfunction "MS3_MS3") (pintype "input"))
      (node (ref "SJ3") (pin "1") (pinfunction "1_1") (pintype "passive"))
    )
    (net (code "85") (name "Net-(P2-~{RESET})") (class "Default")
      (node (ref "P2") (pin "!RST") (pinfunction "~{RESET}_!RST") (pintype "input"))
      (node (ref "P2") (pin "!SLP") (pinfunction "~{SLEEP}_!SLP") (pintype "input"))
    )
    (net (code "86") (name "Net-(P3-MOT-1A)") (class "Default")
      (node (ref "JP20") (pin "2") (pinfunction "2_2") (pintype "passive"))
      (node (ref "P3") (pin "1A") (pinfunction "MOT-1A_1A") (pintype "power_in"))
    )
    (net (code "87") (name "Net-(P3-MOT-1B)") (class "Default")
      (node (ref "JP20") (pin "1") (pinfunction "1_1") (pintype "passive"))
      (node (ref "P3") (pin "1B") (pinfunction "MOT-1B_1B") (pintype "power_in"))
    )
    (net (code "88") (name "Net-(P3-MOT-2A)") (class "Default")
      (node (ref "JP20") (pin "3") (pinfunction "3_3") (pintype "passive"))
      (node (ref "P3") (pin "2A") (pinfunction "MOT-2A_2A") (pintype "power_in"))
    )
    (net (code "89") (name "Net-(P3-MOT-2B)") (class "Default")
      (node (ref "JP20") (pin "4") (pinfunction "4_4") (pintype "passive"))
      (node (ref "P3") (pin "2B") (pinfunction "MOT-2B_2B") (pintype "power_in"))
    )
    (net (code "90") (name "Net-(P3-PadMS1)") (class "Default")
      (node (ref "P3") (pin "MS1") (pinfunction "MS1_MS1") (pintype "input"))
      (node (ref "SJ14") (pin "1") (pinfunction "1_1") (pintype "passive"))
    )
    (net (code "91") (name "Net-(P3-PadMS2)") (class "Default")
      (node (ref "P3") (pin "MS2") (pinfunction "MS2_MS2") (pintype "input"))
      (node (ref "SJ9") (pin "1") (pinfunction "1_1") (pintype "passive"))
    )
    (net (code "92") (name "Net-(P3-PadMS3)") (class "Default")
      (node (ref "P3") (pin "MS3") (pinfunction "MS3_MS3") (pintype "input"))
      (node (ref "SJ4") (pin "1") (pinfunction "1_1") (pintype "passive"))
    )
    (net (code "93") (name "Net-(P3-~{RESET})") (class "Default")
      (node (ref "P3") (pin "!RST") (pinfunction "~{RESET}_!RST") (pintype "input"))
      (node (ref "P3") (pin "!SLP") (pinfunction "~{SLEEP}_!SLP") (pintype "input"))
    )
    (net (code "94") (name "Net-(P4-MOT-1A)") (class "Default")
      (node (ref "JP18") (pin "2") (pinfunction "2_2") (pintype "passive"))
      (node (ref "P4") (pin "1A") (pinfunction "MOT-1A_1A") (pintype "power_in"))
    )
    (net (code "95") (name "Net-(P4-MOT-1B)") (class "Default")
      (node (ref "JP18") (pin "1") (pinfunction "1_1") (pintype "passive"))
      (node (ref "P4") (pin "1B") (pinfunction "MOT-1B_1B") (pintype "power_in"))
    )
    (net (code "96") (name "Net-(P4-MOT-2A)") (class "Default")
      (node (ref "JP18") (pin "3") (pinfunction "3_3") (pintype "passive"))
      (node (ref "P4") (pin "2A") (pinfunction "MOT-2A_2A") (pintype "power_in"))
    )
    (net (code "97") (name "Net-(P4-MOT-2B)") (class "Default")
      (node (ref "JP18") (pin "4") (pinfunction "4_4") (pintype "passive"))
      (node (ref "P4") (pin "2B") (pinfunction "MOT-2B_2B") (pintype "power_in"))
    )
    (net (code "98") (name "Net-(P4-PadMS1)") (class "Default")
      (node (ref "P4") (pin "MS1") (pinfunction "MS1_MS1") (pintype "input"))
      (node (ref "SJ15") (pin "1") (pinfunction "1_1") (pintype "passive"))
    )
    (net (code "99") (name "Net-(P4-PadMS2)") (class "Default")
      (node (ref "P4") (pin "MS2") (pinfunction "MS2_MS2") (pintype "input"))
      (node (ref "SJ10") (pin "1") (pinfunction "1_1") (pintype "passive"))
    )
    (net (code "100") (name "Net-(P4-PadMS3)") (class "Default")
      (node (ref "P4") (pin "MS3") (pinfunction "MS3_MS3") (pintype "input"))
      (node (ref "SJ5") (pin "1") (pinfunction "1_1") (pintype "passive"))
    )
    (net (code "101") (name "Net-(P4-~{RESET})") (class "Default")
      (node (ref "P4") (pin "!RST") (pinfunction "~{RESET}_!RST") (pintype "input"))
      (node (ref "P4") (pin "!SLP") (pinfunction "~{SLEEP}_!SLP") (pintype "input"))
    )
    (net (code "102") (name "Net-(P5-MOT-1A)") (class "Default")
      (node (ref "JP19") (pin "2") (pinfunction "2_2") (pintype "passive"))
      (node (ref "P5") (pin "1A") (pinfunction "MOT-1A_1A") (pintype "power_in"))
    )
    (net (code "103") (name "Net-(P5-MOT-1B)") (class "Default")
      (node (ref "JP19") (pin "1") (pinfunction "1_1") (pintype "passive"))
      (node (ref "P5") (pin "1B") (pinfunction "MOT-1B_1B") (pintype "power_in"))
    )
    (net (code "104") (name "Net-(P5-MOT-2A)") (class "Default")
      (node (ref "JP19") (pin "3") (pinfunction "3_3") (pintype "passive"))
      (node (ref "P5") (pin "2A") (pinfunction "MOT-2A_2A") (pintype "power_in"))
    )
    (net (code "105") (name "Net-(P5-MOT-2B)") (class "Default")
      (node (ref "JP19") (pin "4") (pinfunction "4_4") (pintype "passive"))
      (node (ref "P5") (pin "2B") (pinfunction "MOT-2B_2B") (pintype "power_in"))
    )
    (net (code "106") (name "Net-(P5-PadMS1)") (class "Default")
      (node (ref "P5") (pin "MS1") (pinfunction "MS1_MS1") (pintype "input"))
      (node (ref "SJ16") (pin "1") (pinfunction "1_1") (pintype "passive"))
    )
    (net (code "107") (name "Net-(P5-PadMS2)") (class "Default")
      (node (ref "P5") (pin "MS2") (pinfunction "MS2_MS2") (pintype "input"))
      (node (ref "SJ11") (pin "1") (pinfunction "1_1") (pintype "passive"))
    )
    (net (code "108") (name "Net-(P5-PadMS3)") (class "Default")
      (node (ref "P5") (pin "MS3") (pinfunction "MS3_MS3") (pintype "input"))
      (node (ref "SJ6") (pin "1") (pinfunction "1_1") (pintype "passive"))
    )
    (net (code "109") (name "Net-(P5-~{RESET})") (class "Default")
      (node (ref "P5") (pin "!RST") (pinfunction "~{RESET}_!RST") (pintype "input"))
      (node (ref "P5") (pin "!SLP") (pinfunction "~{SLEEP}_!SLP") (pintype "input"))
    )
    (net (code "110") (name "Net-(Q1-D)") (class "Default")
      (node (ref "D2") (pin "C") (pinfunction "C_C") (pintype "passive"))
      (node (ref "F1") (pin "P$1") (pinfunction "P$1_P$1") (pintype "passive"))
      (node (ref "Q1") (pin "3") (pinfunction "D_3") (pintype "passive"))
    )
    (net (code "111") (name "Net-(Q1-G)") (class "Default")
      (node (ref "Q1") (pin "1") (pinfunction "G_1") (pintype "passive"))
      (node (ref "R3") (pin "2") (pinfunction "2_2") (pintype "passive"))
    )
    (net (code "112") (name "Net-(Q2-D)") (class "Default")
      (node (ref "J5") (pin "1") (pinfunction "1_1") (pintype "power_in"))
      (node (ref "J5") (pin "2") (pinfunction "2_2") (pintype "power_in"))
      (node (ref "Q2") (pin "5-8") (pinfunction "D_5-8") (pintype "passive"))
    )
    (net (code "113") (name "Net-(Q2-G)") (class "Default")
      (node (ref "Q2") (pin "4") (pinfunction "G_4") (pintype "passive"))
      (node (ref "R9") (pin "2") (pinfunction "2_2") (pintype "passive"))
    )
    (net (code "114") (name "Net-(Q3-D)") (class "Default")
      (node (ref "J7") (pin "1") (pinfunction "1_1") (pintype "power_in"))
      (node (ref "J7") (pin "2") (pinfunction "2_2") (pintype "power_in"))
      (node (ref "Q3") (pin "5-8") (pinfunction "D_5-8") (pintype "passive"))
    )
    (net (code "115") (name "Net-(Q3-G)") (class "Default")
      (node (ref "Q3") (pin "4") (pinfunction "G_4") (pintype "passive"))
      (node (ref "R11") (pin "2") (pinfunction "2_2") (pintype "passive"))
    )
    (net (code "116") (name "Net-(Q4-D)") (class "Default")
      (node (ref "J8") (pin "1") (pinfunction "1_1") (pintype "power_in"))
      (node (ref "J8") (pin "2") (pinfunction "2_2") (pintype "power_in"))
      (node (ref "Q4") (pin "5-8") (pinfunction "D_5-8") (pintype "passive"))
    )
    (net (code "117") (name "Net-(Q4-G)") (class "Default")
      (node (ref "Q4") (pin "4") (pinfunction "G_4") (pintype "passive"))
      (node (ref "R15") (pin "2") (pinfunction "2_2") (pintype "passive"))
    )
    (net (code "118") (name "Net-(U1-CB)") (class "Default")
      (node (ref "C4") (pin "2") (pinfunction "2_2") (pintype "passive"))
      (node (ref "U1") (pin "1") (pinfunction "CB_1") (pintype "passive"))
    )
    (net (code "119") (name "Net-(U1-FB)") (class "Default")
      (node (ref "R4") (pin "2") (pinfunction "2_2") (pintype "passive"))
      (node (ref "R5") (pin "1") (pinfunction "1_1") (pintype "passive"))
      (node (ref "U1") (pin "3") (pinfunction "FB_3") (pintype "passive"))
    )
    (net (code "120") (name "Net-(U1-SW)") (class "Default")
      (node (ref "C4") (pin "1") (pinfunction "1_1") (pintype "passive"))
      (node (ref "D1") (pin "C") (pinfunction "C_C") (pintype "passive"))
      (node (ref "L1") (pin "1") (pinfunction "1_1") (pintype "passive"))
      (node (ref "U1") (pin "6") (pinfunction "SW_6") (pintype "passive"))
    )
    (net (code "121") (name "unconnected-(J1-DAT1-Pad8)") (class "Default")
      (node (ref "J1") (pin "8") (pinfunction "DAT1_8") (pintype "bidirectional"))
    )
    (net (code "122") (name "unconnected-(J1-DAT2-Pad1)") (class "Default")
      (node (ref "J1") (pin "1") (pinfunction "DAT2_1") (pintype "bidirectional"))
    )
    (net (code "123") (name "unconnected-(U2-IO3-Pad4)") (class "Default")
      (node (ref "U2") (pin "4") (pinfunction "IO3_4") (pintype "bidirectional"))
    )
    (net (code "124") (name "unconnected-(U2-IO4-Pad6)") (class "Default")
      (node (ref "U2") (pin "6") (pinfunction "IO4_6") (pintype "bidirectional"))
    )
  )
)
